# BW2098_USB.net
KiCad netlist of a schematic drawn in Altium Designer
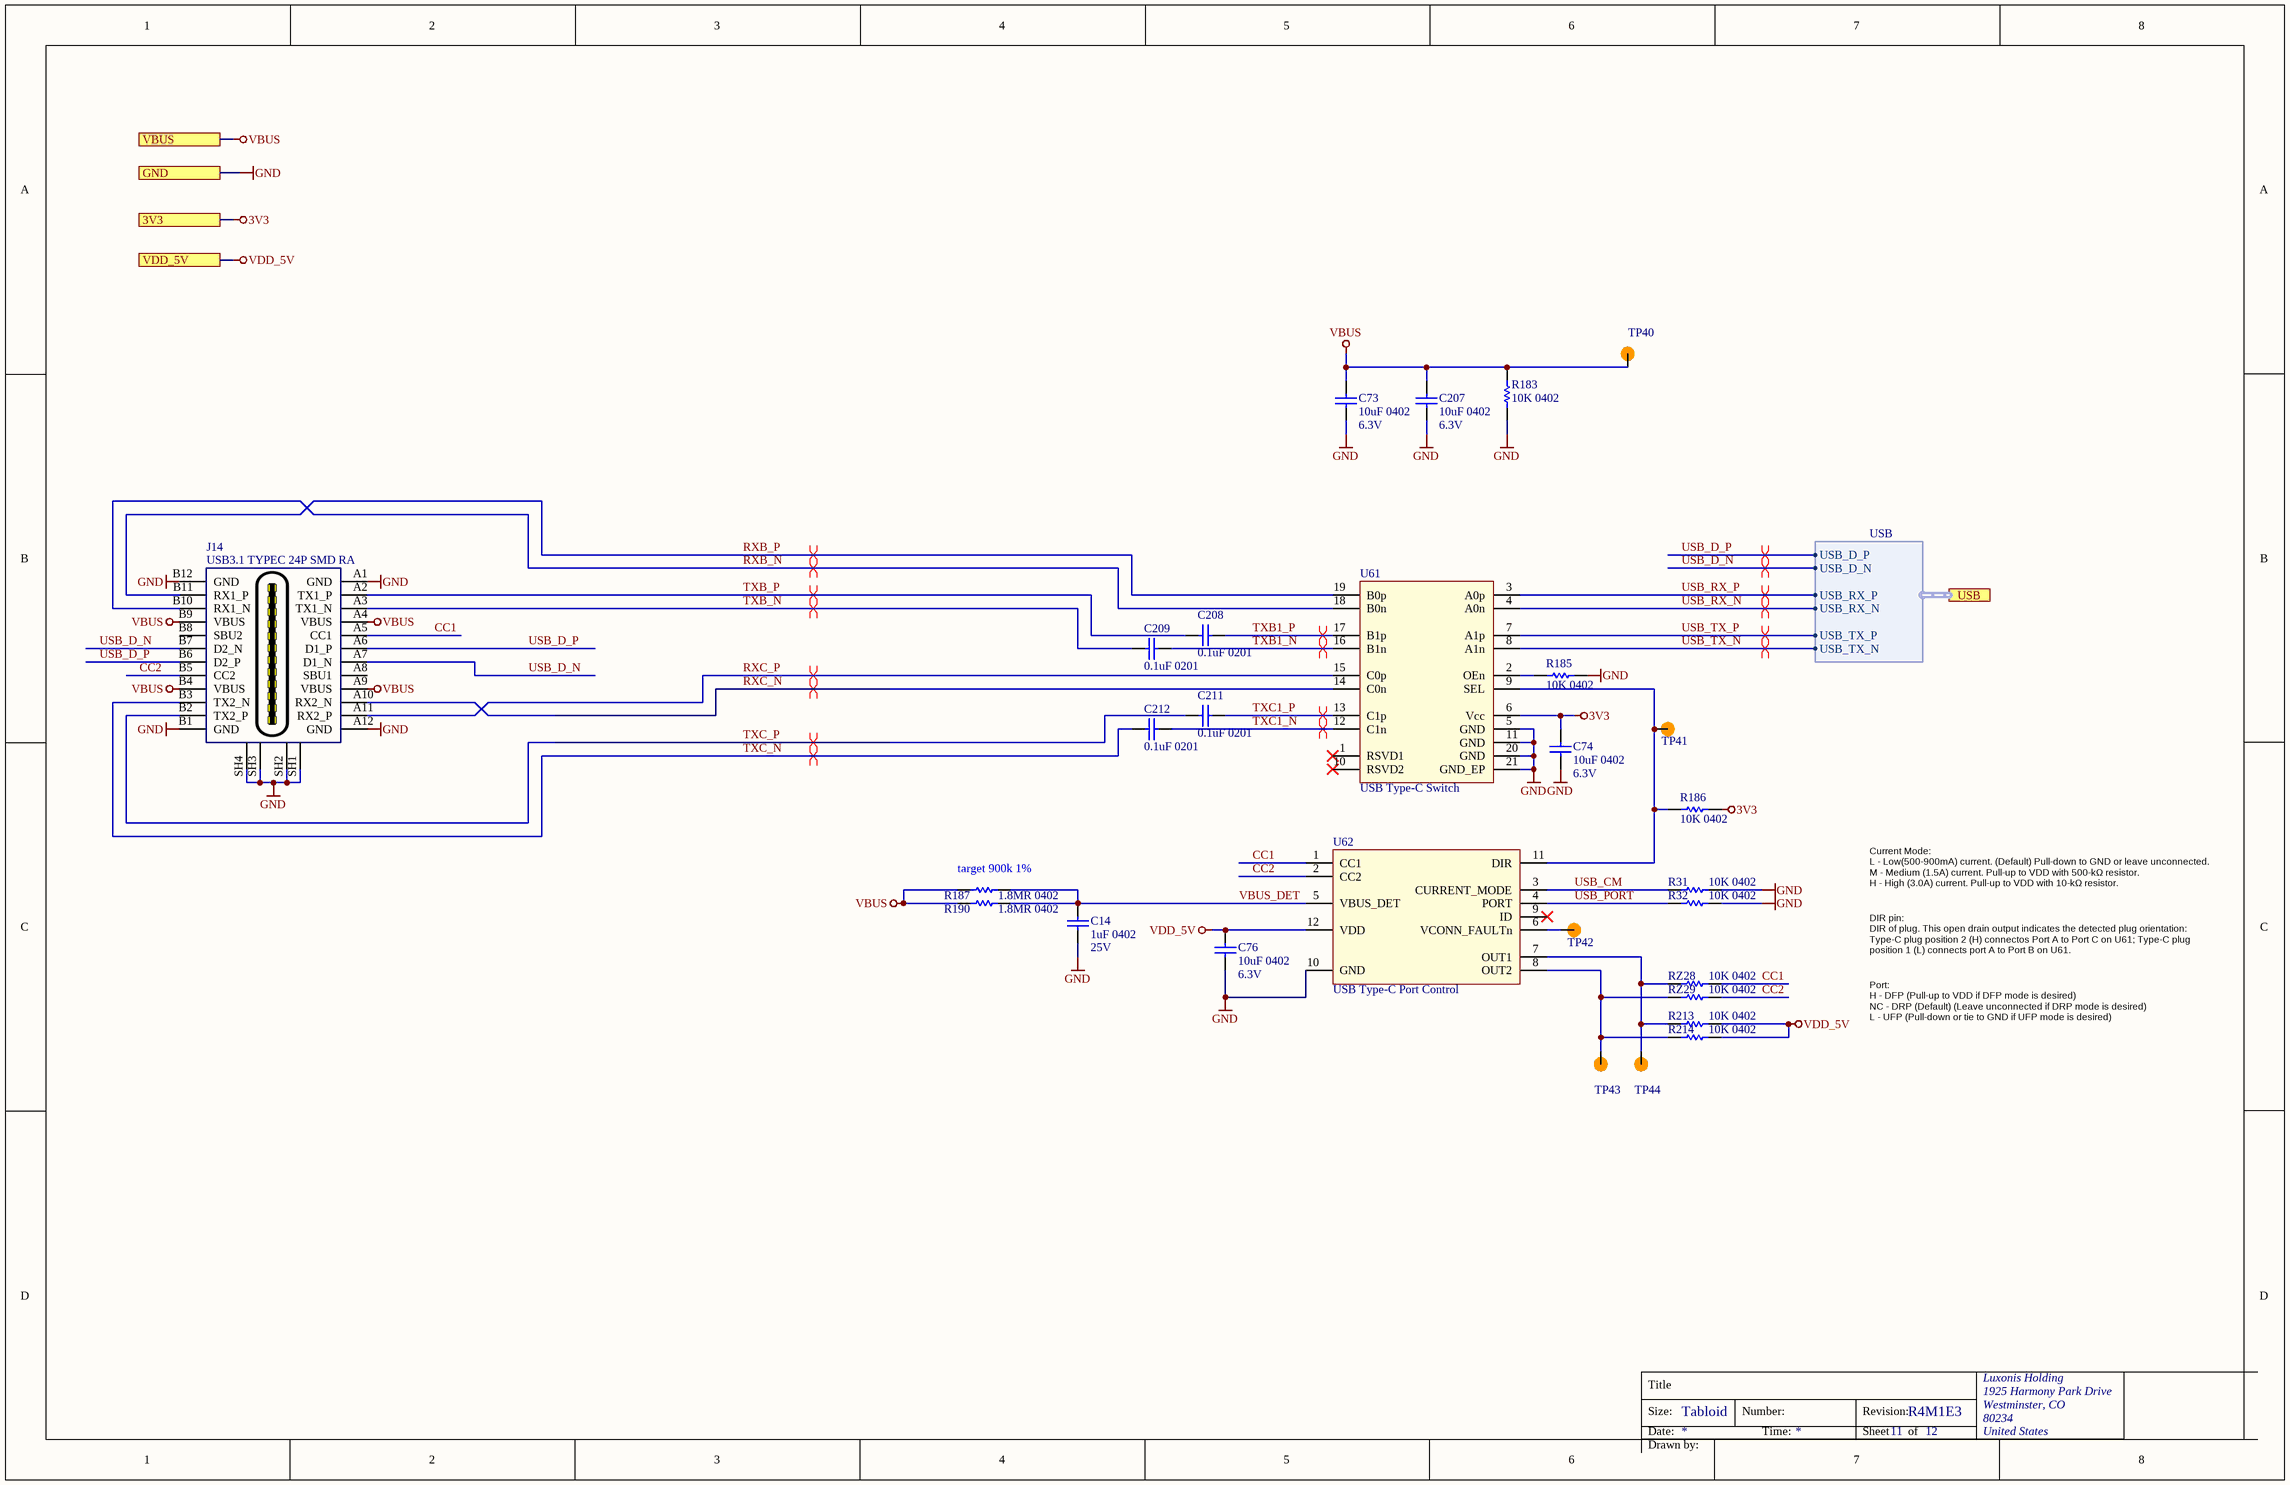
[diagram p0: BW2098_USB.SchDoc]

(export (version "E")
  (design (tool "Eeschema 10.0.6"))
  (components
    (comp (ref "C14")
      (value "1uF 0402")
      (footprint "CAP_Altium_Vault_Generic:CAPC0402(1005)70_N")
      (description "CAP CER 1UF 25V X5R 0402 10%")
      (fields
        (field (name "TOLERANCE") "10%")
        (field (name "VOLTAGE") "25V")
        (field (name "VOLTAGE RATING") "25V")
      )
      (libsource (lib "LuxonisMaster") (part "GRM155R61E105KA12D"))
    )
    (comp (ref "C73")
      (value "10uF 0402")
      (footprint "CAP_Altium_Vault_Generic:CAPC0402(1005)70_N")
      (description "CAP CER 10UF 6.3V X5R 0402 20%")
      (fields (field (name "TOLERANCE") "20%") (field (name "VOLTAGE RATING") "6.3V"))
      (libsource (lib "LuxonisMaster") (part "GRM155R60J106ME15D"))
    )
    (comp (ref "C74")
      (value "10uF 0402")
      (footprint "CAP_Altium_Vault_Generic:CAPC0402(1005)70_N")
      (description "CAP CER 10UF 6.3V X5R 0402 20%")
      (fields (field (name "TOLERANCE") "20%") (field (name "VOLTAGE RATING") "6.3V"))
      (libsource (lib "LuxonisMaster") (part "GRM155R60J106ME15D"))
    )
    (comp (ref "C76")
      (value "10uF 0402")
      (footprint "CAP_Altium_Vault_Generic:CAPC0402(1005)70_N")
      (description "CAP CER 10UF 6.3V X5R 0402 20%")
      (fields (field (name "TOLERANCE") "20%") (field (name "VOLTAGE RATING") "6.3V"))
      (libsource (lib "LuxonisMaster") (part "GRM155R60J106ME15D"))
    )
    (comp (ref "C207")
      (value "10uF 0402")
      (footprint "CAP_Altium_Vault_Generic:CAPC0402(1005)70_N")
      (description "CAP CER 10UF 6.3V X5R 0402 20%")
      (fields (field (name "TOLERANCE") "20%") (field (name "VOLTAGE RATING") "6.3V"))
      (libsource (lib "LuxonisMaster") (part "GRM155R60J106ME15D"))
    )
    (comp (ref "C208")
      (value "0.1uF 0201")
      (footprint "CAP_Altium_Vault_Generic:CAPC0201(0603)33_L")
      (description "CAP CER 0.1UF 10V X5R 0201")
      (fields (field (name "TOLERANCE") "10%") (field (name "VOLTAGE") "10V"))
      (libsource (lib "LuxonisMaster") (part "GRM033R61A104KE15D"))
    )
    (comp (ref "C209")
      (value "0.1uF 0201")
      (footprint "CAP_Altium_Vault_Generic:CAPC0201(0603)33_L")
      (description "CAP CER 0.1UF 10V X5R 0201")
      (fields (field (name "TOLERANCE") "10%") (field (name "VOLTAGE") "10V"))
      (libsource (lib "LuxonisMaster") (part "GRM033R61A104KE15D"))
    )
    (comp (ref "C211")
      (value "0.1uF 0201")
      (footprint "CAP_Altium_Vault_Generic:CAPC0201(0603)33_L")
      (description "CAP CER 0.1UF 10V X5R 0201")
      (fields (field (name "TOLERANCE") "10%") (field (name "VOLTAGE") "10V"))
      (libsource (lib "LuxonisMaster") (part "GRM033R61A104KE15D"))
    )
    (comp (ref "C212")
      (value "0.1uF 0201")
      (footprint "CAP_Altium_Vault_Generic:CAPC0201(0603)33_L")
      (description "CAP CER 0.1UF 10V X5R 0201")
      (fields (field (name "TOLERANCE") "10%") (field (name "VOLTAGE") "10V"))
      (libsource (lib "LuxonisMaster") (part "GRM033R61A104KE15D"))
    )
    (comp (ref "J14")
      (value "USB3.1 TYPEC 24P SMD RA")
      (footprint "LuxonisMaster:105450-0101")
      (description "CONN RCP USB3.1 TYPEC 24P SMD RA")
      (libsource (lib "LuxonisMaster") (part "105450-0101"))
    )
    (comp (ref "R31")
      (value "10K 0402")
      (footprint "RES_Altium_Vault_Generic:RESC0402(1005)_N")
      (fields (field (name "TOLERANCE") "1%"))
      (libsource (lib "LuxonisMaster") (part "RC0402FR-1310KL"))
    )
    (comp (ref "R32")
      (value "10K 0402")
      (footprint "RES_Altium_Vault_Generic:RESC0402(1005)_N")
      (fields (field (name "TOLERANCE") "1%"))
      (libsource (lib "LuxonisMaster") (part "RC0402FR-1310KL"))
    )
    (comp (ref "R183")
      (value "10K 0402")
      (footprint "RES_Altium_Vault_Generic:RESC0402(1005)_N")
      (fields (field (name "TOLERANCE") "1%"))
      (libsource (lib "LuxonisMaster") (part "RC0402FR-1310KL"))
    )
    (comp (ref "R185")
      (value "10K 0402")
      (footprint "RES_Altium_Vault_Generic:RESC0402(1005)_N")
      (fields (field (name "TOLERANCE") "1%"))
      (libsource (lib "LuxonisMaster") (part "RC0402FR-1310KL"))
    )
    (comp (ref "R186")
      (value "10K 0402")
      (footprint "RES_Altium_Vault_Generic:RESC0402(1005)_N")
      (fields (field (name "TOLERANCE") "1%"))
      (libsource (lib "LuxonisMaster") (part "RC0402FR-1310KL"))
    )
    (comp (ref "R187")
      (value "1.8MR 0402")
      (footprint "RES_Altium_Vault_Generic:RESC0402(1005)_N")
      (description "RES SMD 1.8M OHM 1% 1/16W 0402")
      (fields (field (name "TOLERANCE") "1%"))
      (libsource (lib "LuxonisMaster") (part "CRCW04021M80FKED"))
    )
    (comp (ref "R190")
      (value "1.8MR 0402")
      (footprint "RES_Altium_Vault_Generic:RESC0402(1005)_N")
      (description "RES SMD 1.8M OHM 1% 1/16W 0402")
      (fields (field (name "TOLERANCE") "1%"))
      (libsource (lib "LuxonisMaster") (part "CRCW04021M80FKED"))
    )
    (comp (ref "R213")
      (value "10K 0402")
      (footprint "RES_Altium_Vault_Generic:RESC0402(1005)_N")
      (fields (field (name "TOLERANCE") "1%"))
      (libsource (lib "LuxonisMaster") (part "RC0402FR-1310KL"))
    )
    (comp (ref "R214")
      (value "10K 0402")
      (footprint "RES_Altium_Vault_Generic:RESC0402(1005)_N")
      (fields (field (name "TOLERANCE") "1%"))
      (libsource (lib "LuxonisMaster") (part "RC0402FR-1310KL"))
    )
    (comp (ref "RZ28")
      (value "10K 0402")
      (footprint "RES_Altium_Vault_Generic:RESC0402(1005)_N")
      (fields (field (name "TOLERANCE") "1%"))
      (libsource (lib "LuxonisMaster") (part "RC0402FR-1310KL"))
    )
    (comp (ref "RZ29")
      (value "10K 0402")
      (footprint "RES_Altium_Vault_Generic:RESC0402(1005)_N")
      (fields (field (name "TOLERANCE") "1%"))
      (libsource (lib "LuxonisMaster") (part "RC0402FR-1310KL"))
    )
    (comp (ref "TP40")
      (value "TP100_200_NS")
      (footprint "LuxonisMaster:TP100_200_NS")
      (libsource (lib "LuxonisMaster") (part "TEST_POINT"))
    )
    (comp (ref "TP41")
      (value "TP100_200_NS")
      (footprint "LuxonisMaster:TP100_200_NS")
      (libsource (lib "LuxonisMaster") (part "TEST_POINT"))
    )
    (comp (ref "TP42")
      (value "TP100_200_NS")
      (footprint "LuxonisMaster:TP100_200_NS")
      (libsource (lib "LuxonisMaster") (part "TEST_POINT"))
    )
    (comp (ref "TP43")
      (value "TP100_200_NS")
      (footprint "LuxonisMaster:TP100_200_NS")
      (libsource (lib "LuxonisMaster") (part "TEST_POINT"))
    )
    (comp (ref "TP44")
      (value "TP100_200_NS")
      (footprint "LuxonisMaster:TP100_200_NS")
      (libsource (lib "LuxonisMaster") (part "TEST_POINT"))
    )
    (comp (ref "U61")
      (value "USB Type-C Switch")
      (footprint "LuxonisMaster:HD3SS3212RKSR")
      (description "IC MUX 2:1 8 OHM 20VQFN")
      (libsource (lib "LuxonisMaster") (part "HD3SS3212RKSR"))
    )
    (comp (ref "U62")
      (value "USB Type-C Port Control")
      (footprint "LuxonisMaster:TUSB321RWBR")
      (description "IC USB PORT CONTROL TYPE-C 12X2Q")
      (libsource (lib "LuxonisMaster") (part "TUSB321RWBR"))
    )
  )
  (nets
    (net (code "2") (name "/CC1") (class "Default")
      (node (ref "J14") (pin "A5") (pinfunction "CC1_A5") (pintype "passive"))
      (node (ref "RZ28") (pin "2") (pinfunction "2_2") (pintype "passive"))
      (node (ref "U62") (pin "1") (pinfunction "CC1_1") (pintype "passive"))
    )
    (net (code "3") (name "/CC2") (class "Default")
      (node (ref "J14") (pin "B5") (pinfunction "CC2_B5") (pintype "passive"))
      (node (ref "RZ29") (pin "2") (pinfunction "2_2") (pintype "passive"))
      (node (ref "U62") (pin "2") (pinfunction "CC2_2") (pintype "passive"))
    )
    (net (code "4") (name "/RXB_N") (class "Default")
      (node (ref "J14") (pin "B10") (pinfunction "RX1_N_B10") (pintype "passive"))
      (node (ref "U61") (pin "18") (pinfunction "B0n_18") (pintype "passive"))
    )
    (net (code "5") (name "/RXB_P") (class "Default")
      (node (ref "J14") (pin "B11") (pinfunction "RX1_P_B11") (pintype "passive"))
      (node (ref "U61") (pin "19") (pinfunction "B0p_19") (pintype "passive"))
    )
    (net (code "6") (name "/RXC_N") (class "Default")
      (node (ref "J14") (pin "A10") (pinfunction "RX2_N_A10") (pintype "passive"))
      (node (ref "U61") (pin "14") (pinfunction "C0n_14") (pintype "passive"))
    )
    (net (code "7") (name "/RXC_P") (class "Default")
      (node (ref "J14") (pin "A11") (pinfunction "RX2_P_A11") (pintype "passive"))
      (node (ref "U61") (pin "15") (pinfunction "C0p_15") (pintype "passive"))
    )
    (net (code "8") (name "/TXB1_N") (class "Default")
      (node (ref "C209") (pin "2") (pinfunction "2_2") (pintype "passive"))
      (node (ref "U61") (pin "16") (pinfunction "B1n_16") (pintype "passive"))
    )
    (net (code "9") (name "/TXB1_P") (class "Default")
      (node (ref "C208") (pin "2") (pinfunction "2_2") (pintype "passive"))
      (node (ref "U61") (pin "17") (pinfunction "B1p_17") (pintype "passive"))
    )
    (net (code "10") (name "/TXB_N") (class "Default")
      (node (ref "C209") (pin "1") (pinfunction "1_1") (pintype "passive"))
      (node (ref "J14") (pin "A3") (pinfunction "TX1_N_A3") (pintype "passive"))
    )
    (net (code "11") (name "/TXB_P") (class "Default")
      (node (ref "C208") (pin "1") (pinfunction "1_1") (pintype "passive"))
      (node (ref "J14") (pin "A2") (pinfunction "TX1_P_A2") (pintype "passive"))
    )
    (net (code "12") (name "/TXC1_N") (class "Default")
      (node (ref "C212") (pin "2") (pinfunction "2_2") (pintype "passive"))
      (node (ref "U61") (pin "12") (pinfunction "C1n_12") (pintype "passive"))
    )
    (net (code "13") (name "/TXC1_P") (class "Default")
      (node (ref "C211") (pin "2") (pinfunction "2_2") (pintype "passive"))
      (node (ref "U61") (pin "13") (pinfunction "C1p_13") (pintype "passive"))
    )
    (net (code "14") (name "/TXC_N") (class "Default")
      (node (ref "C212") (pin "1") (pinfunction "1_1") (pintype "passive"))
      (node (ref "J14") (pin "B3") (pinfunction "TX2_N_B3") (pintype "passive"))
    )
    (net (code "15") (name "/TXC_P") (class "Default")
      (node (ref "C211") (pin "1") (pinfunction "1_1") (pintype "passive"))
      (node (ref "J14") (pin "B2") (pinfunction "TX2_P_B2") (pintype "passive"))
    )
    (net (code "16") (name "/USB_CM") (class "Default")
      (node (ref "R31") (pin "1") (pinfunction "1_1") (pintype "passive"))
      (node (ref "U62") (pin "3") (pinfunction "CURRENT_MODE_3") (pintype "passive"))
    )
    (net (code "17") (name "/USB_D_N") (class "Default")
      (node (ref "J14") (pin "A7") (pinfunction "D1_N_A7") (pintype "passive"))
      (node (ref "J14") (pin "B7") (pinfunction "D2_N_B7") (pintype "passive"))
    )
    (net (code "18") (name "/USB_D_P") (class "Default")
      (node (ref "J14") (pin "A6") (pinfunction "D1_P_A6") (pintype "passive"))
      (node (ref "J14") (pin "B6") (pinfunction "D2_P_B6") (pintype "passive"))
    )
    (net (code "19") (name "/USB_PORT") (class "Default")
      (node (ref "R32") (pin "1") (pinfunction "1_1") (pintype "passive"))
      (node (ref "U62") (pin "4") (pinfunction "PORT_4") (pintype "passive"))
    )
    (net (code "20") (name "/USB_RX_N") (class "Default")
      (node (ref "U61") (pin "4") (pinfunction "A0n_4") (pintype "passive"))
    )
    (net (code "21") (name "/USB_RX_P") (class "Default")
      (node (ref "U61") (pin "3") (pinfunction "A0p_3") (pintype "passive"))
    )
    (net (code "22") (name "/USB_TX_N") (class "Default")
      (node (ref "U61") (pin "8") (pinfunction "A1n_8") (pintype "passive"))
    )
    (net (code "23") (name "/USB_TX_P") (class "Default")
      (node (ref "U61") (pin "7") (pinfunction "A1p_7") (pintype "passive"))
    )
    (net (code "24") (name "/VBUS_DET") (class "Default")
      (node (ref "C14") (pin "2") (pinfunction "2_2") (pintype "passive"))
      (node (ref "R187") (pin "2") (pinfunction "2_2") (pintype "passive"))
      (node (ref "R190") (pin "2") (pinfunction "2_2") (pintype "passive"))
      (node (ref "U62") (pin "5") (pinfunction "VBUS_DET_5") (pintype "passive"))
    )
    (net (code "26") (name "3V3") (class "Default")
      (node (ref "C74") (pin "2") (pinfunction "2_2") (pintype "passive"))
      (node (ref "R186") (pin "2") (pinfunction "2_2") (pintype "passive"))
      (node (ref "U61") (pin "6") (pinfunction "Vcc_6") (pintype "passive"))
    )
    (net (code "27") (name "GND") (class "Default")
      (node (ref "C14") (pin "1") (pinfunction "1_1") (pintype "passive"))
      (node (ref "C207") (pin "1") (pinfunction "1_1") (pintype "passive"))
      (node (ref "C73") (pin "1") (pinfunction "1_1") (pintype "passive"))
      (node (ref "C74") (pin "1") (pinfunction "1_1") (pintype "passive"))
      (node (ref "C76") (pin "1") (pinfunction "1_1") (pintype "passive"))
      (node (ref "J14") (pin "A1") (pinfunction "GND_A1") (pintype "passive"))
      (node (ref "J14") (pin "A12") (pinfunction "GND_A12") (pintype "passive"))
      (node (ref "J14") (pin "B1") (pinfunction "GND_B1") (pintype "passive"))
      (node (ref "J14") (pin "B12") (pinfunction "GND_B12") (pintype "passive"))
      (node (ref "J14") (pin "SH1") (pinfunction "SH_SH1") (pintype "passive"))
      (node (ref "J14") (pin "SH2") (pinfunction "SH_SH2") (pintype "passive"))
      (node (ref "J14") (pin "SH3") (pinfunction "SH_SH3") (pintype "passive"))
      (node (ref "J14") (pin "SH4") (pinfunction "SH_SH4") (pintype "passive"))
      (node (ref "R183") (pin "1") (pinfunction "1_1") (pintype "passive"))
      (node (ref "R185") (pin "2") (pinfunction "2_2") (pintype "passive"))
      (node (ref "R31") (pin "2") (pinfunction "2_2") (pintype "passive"))
      (node (ref "R32") (pin "2") (pinfunction "2_2") (pintype "passive"))
      (node (ref "U61") (pin "11") (pinfunction "GND_11") (pintype "passive"))
      (node (ref "U61") (pin "20") (pinfunction "GND_20") (pintype "passive"))
      (node (ref "U61") (pin "21") (pinfunction "GND_EP_21") (pintype "passive"))
      (node (ref "U61") (pin "5") (pinfunction "GND_5") (pintype "passive"))
      (node (ref "U62") (pin "10") (pinfunction "GND_10") (pintype "passive"))
    )
    (net (code "28") (name "Net-(U61-OEn)") (class "Default")
      (node (ref "R185") (pin "1") (pinfunction "1_1") (pintype "passive"))
      (node (ref "U61") (pin "2") (pinfunction "OEn_2") (pintype "passive"))
    )
    (net (code "29") (name "Net-(U61-SEL)") (class "Default")
      (node (ref "R186") (pin "1") (pinfunction "1_1") (pintype "passive"))
      (node (ref "TP41") (pin "1") (pintype "passive"))
      (node (ref "U61") (pin "9") (pinfunction "SEL_9") (pintype "passive"))
      (node (ref "U62") (pin "11") (pinfunction "DIR_11") (pintype "passive"))
    )
    (net (code "30") (name "Net-(U62-OUT1)") (class "Default")
      (node (ref "R213") (pin "1") (pinfunction "1_1") (pintype "passive"))
      (node (ref "RZ28") (pin "1") (pinfunction "1_1") (pintype "passive"))
      (node (ref "TP44") (pin "1") (pintype "passive"))
      (node (ref "U62") (pin "7") (pinfunction "OUT1_7") (pintype "passive"))
    )
    (net (code "31") (name "Net-(U62-OUT2)") (class "Default")
      (node (ref "R214") (pin "1") (pinfunction "1_1") (pintype "passive"))
      (node (ref "RZ29") (pin "1") (pinfunction "1_1") (pintype "passive"))
      (node (ref "TP43") (pin "1") (pintype "passive"))
      (node (ref "U62") (pin "8") (pinfunction "OUT2_8") (pintype "passive"))
    )
    (net (code "32") (name "Net-(U62-VCONN_FAULTn)") (class "Default")
      (node (ref "TP42") (pin "1") (pintype "passive"))
      (node (ref "U62") (pin "6") (pinfunction "VCONN_FAULTn_6") (pintype "passive"))
    )
    (net (code "33") (name "VBUS") (class "Default")
      (node (ref "C207") (pin "2") (pinfunction "2_2") (pintype "passive"))
      (node (ref "C73") (pin "2") (pinfunction "2_2") (pintype "passive"))
      (node (ref "J14") (pin "A4") (pinfunction "VBUS_A4") (pintype "passive"))
      (node (ref "J14") (pin "A9") (pinfunction "VBUS_A9") (pintype "passive"))
      (node (ref "J14") (pin "B4") (pinfunction "VBUS_B4") (pintype "passive"))
      (node (ref "J14") (pin "B9") (pinfunction "VBUS_B9") (pintype "passive"))
      (node (ref "R183") (pin "2") (pinfunction "2_2") (pintype "passive"))
      (node (ref "R187") (pin "1") (pinfunction "1_1") (pintype "passive"))
      (node (ref "R190") (pin "1") (pinfunction "1_1") (pintype "passive"))
      (node (ref "TP40") (pin "1") (pintype "passive"))
    )
    (net (code "34") (name "VDD_5V") (class "Default")
      (node (ref "C76") (pin "2") (pinfunction "2_2") (pintype "passive"))
      (node (ref "R213") (pin "2") (pinfunction "2_2") (pintype "passive"))
      (node (ref "R214") (pin "2") (pinfunction "2_2") (pintype "passive"))
      (node (ref "U62") (pin "12") (pinfunction "VDD_12") (pintype "passive"))
    )
    (net (code "35") (name "unconnected-(J14-SBU1-PadA8)") (class "Default")
      (node (ref "J14") (pin "A8") (pinfunction "SBU1_A8") (pintype "passive"))
    )
    (net (code "36") (name "unconnected-(J14-SBU2-PadB8)") (class "Default")
      (node (ref "J14") (pin "B8") (pinfunction "SBU2_B8") (pintype "passive"))
    )
    (net (code "37") (name "unconnected-(U61-RSVD1-Pad1)") (class "Default")
      (node (ref "U61") (pin "1") (pinfunction "RSVD1_1") (pintype "passive+no_connect"))
    )
    (net (code "38") (name "unconnected-(U61-RSVD2-Pad10)") (class "Default")
      (node (ref "U61") (pin "10") (pinfunction "RSVD2_10") (pintype "passive+no_connect"))
    )
    (net (code "39") (name "unconnected-(U62-ID-Pad9)") (class "Default")
      (node (ref "U62") (pin "9") (pinfunction "ID_9") (pintype "passive+no_connect"))
    )
  )
)
